# MCP4725_Breakout.net
KiCad netlist of a schematic drawn in EAGLE
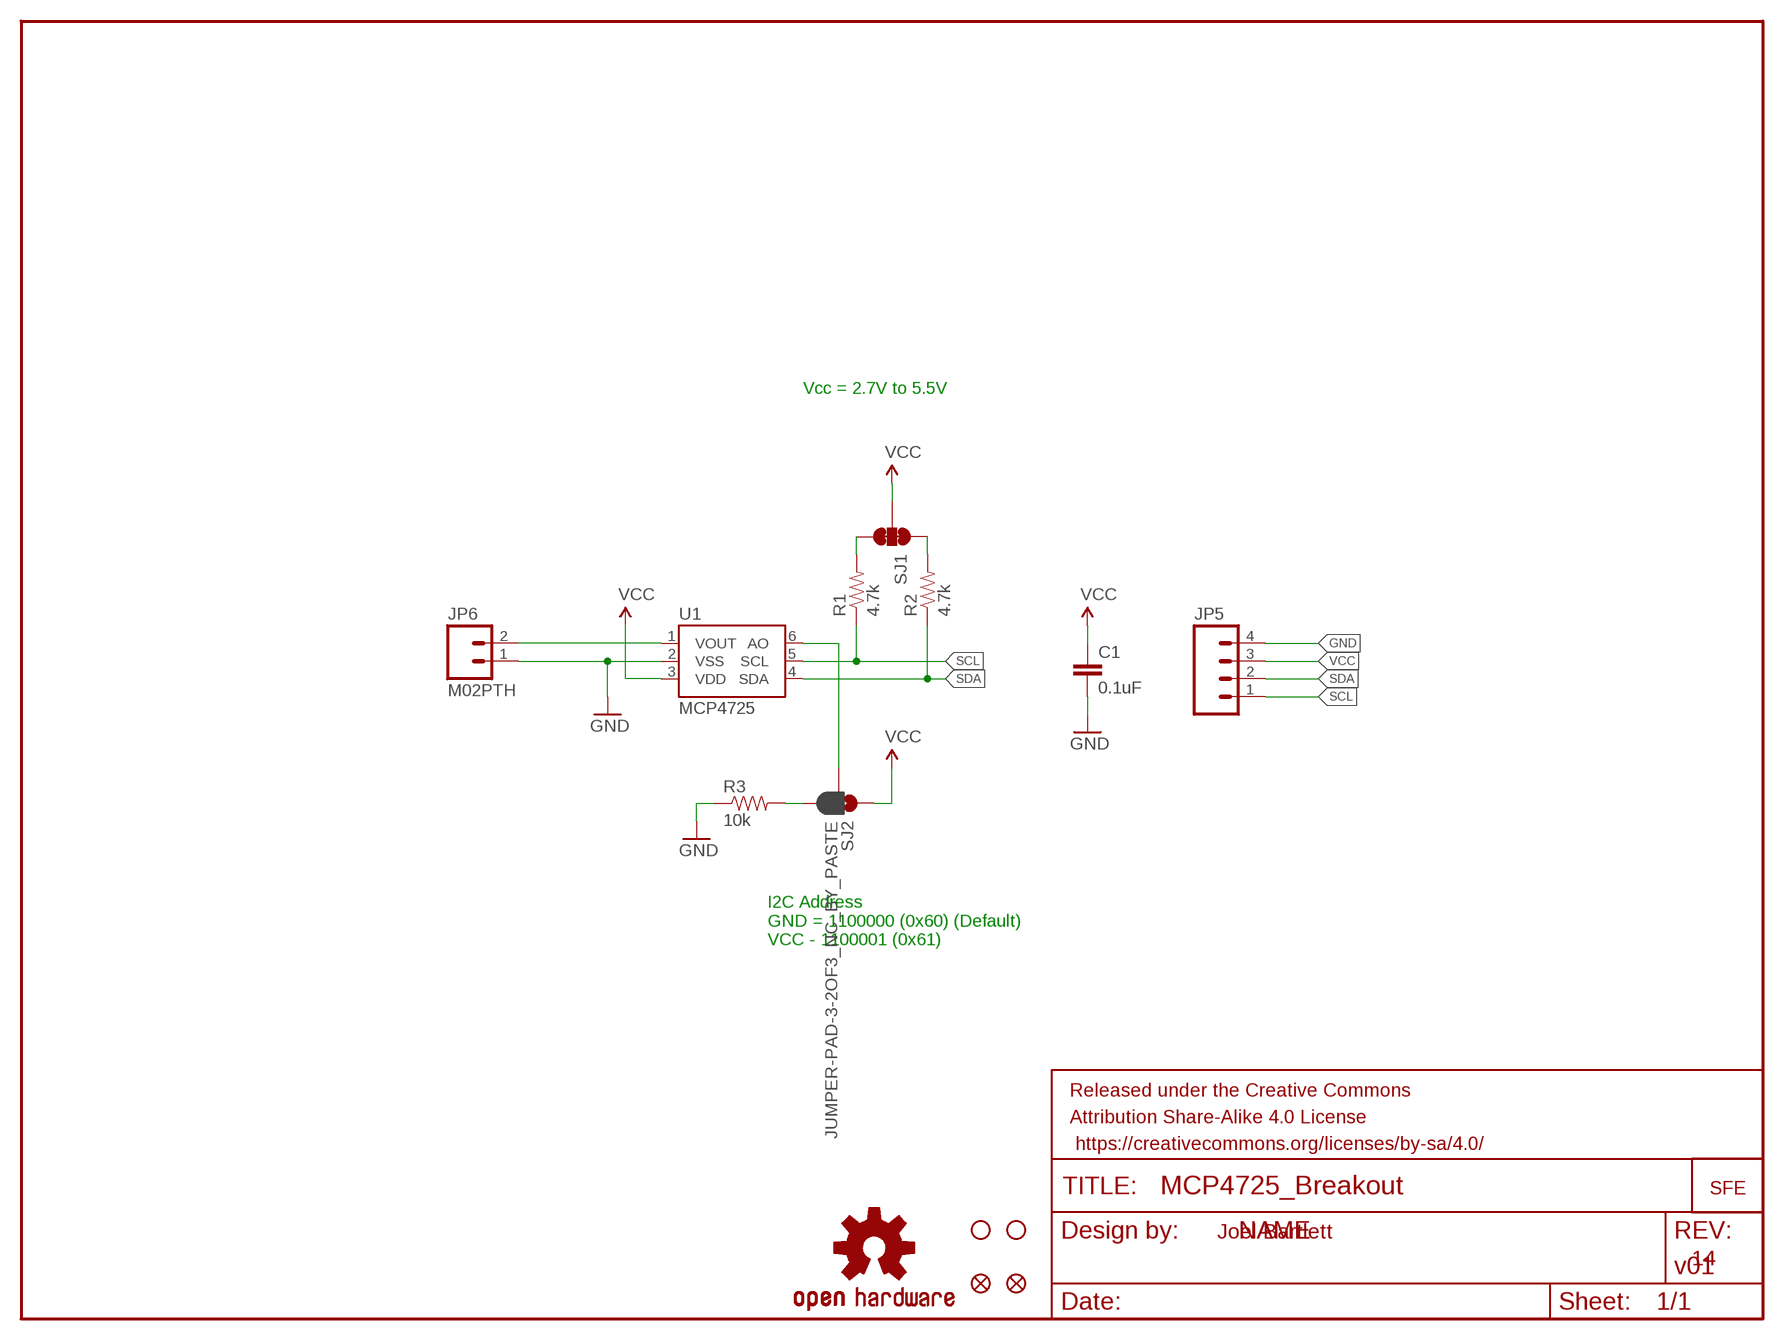
[diagram p0: schematic, sheet 1]

(export (version "E")
  (design (tool "Eeschema 10.0.6"))
  (components
    (comp (ref "C1")
      (value "0.1uF")
      (footprint "eagle-import:0603-CAP")
      (libsource (lib "eagle-import") (part "CAP0603-CAP"))
    )
    (comp (ref "FID1")
      (value "FIDUCIAL1X2")
      (footprint "eagle-import:FIDUCIAL-1X2")
      (libsource (lib "eagle-import") (part "FIDUCIAL1X2"))
    )
    (comp (ref "FID2")
      (value "FIDUCIAL1X2")
      (footprint "eagle-import:FIDUCIAL-1X2")
      (libsource (lib "eagle-import") (part "FIDUCIAL1X2"))
    )
    (comp (ref "FRAME2")
      (value "FRAME-LETTER")
      (footprint "eagle-import:CREATIVE_COMMONS")
      (fields (field (name "DESIGNER") "NAME"))
      (libsource (lib "eagle-import") (part "FRAME-LETTER"))
    )
    (comp (ref "GND")
      (value "LOGO-SFESK")
      (footprint "eagle-import:SFE-LOGO-FLAME")
      (libsource (lib "eagle-import") (part "LOGO-SFESK"))
    )
    (comp (ref "JP5")
      (value "M04PTH")
      (footprint "eagle-import:1X04")
      (libsource (lib "eagle-import") (part "M04PTH"))
    )
    (comp (ref "JP6")
      (value "M02PTH")
      (footprint "eagle-import:1X02")
      (libsource (lib "eagle-import") (part "M02PTH"))
    )
    (comp (ref "LOGO1")
      (value "OSHW-LOGOS")
      (footprint "eagle-import:OSHW-LOGO-S")
      (libsource (lib "eagle-import") (part "OSHW-LOGOS"))
    )
    (comp (ref "R1")
      (value "4.7k")
      (footprint "eagle-import:0603-RES")
      (libsource (lib "eagle-import") (part "RESISTOR0603-RES"))
    )
    (comp (ref "R2")
      (value "4.7k")
      (footprint "eagle-import:0603-RES")
      (libsource (lib "eagle-import") (part "RESISTOR0603-RES"))
    )
    (comp (ref "R3")
      (value "10k")
      (footprint "eagle-import:0603-RES")
      (libsource (lib "eagle-import") (part "RESISTOR0603-RES"))
    )
    (comp (ref "SJ1")
      (value "JUMPER-PAD-3-NC_BY_TRACE")
      (footprint "eagle-import:PAD-JUMPER-3-3OF3_NC_BY_TRACE_YES_SILK_FULL_BOX")
      (libsource (lib "eagle-import") (part "JUMPER-PAD-3-NC_BY_TRACE"))
    )
    (comp (ref "SJ2")
      (value "JUMPER-PAD-3-2OF3_NC_BY_PASTE")
      (footprint "eagle-import:PAD-JUMPER-3-2OF3_NC_BY_PASTE_YES_SILK_FULL_BOX")
      (libsource (lib "eagle-import") (part "JUMPER-PAD-3-2OF3_NC_BY_PASTE"))
    )
    (comp (ref "STANDOFF1")
      (value "STAND-OFF")
      (footprint "eagle-import:STAND-OFF")
      (libsource (lib "eagle-import") (part "STAND-OFF"))
    )
    (comp (ref "STANDOFF2")
      (value "STAND-OFF")
      (footprint "eagle-import:STAND-OFF")
      (libsource (lib "eagle-import") (part "STAND-OFF"))
    )
    (comp (ref "U1")
      (value "MCP4725")
      (footprint "eagle-import:SOT23-6")
      (libsource (lib "eagle-import") (part "MCP4725SOT-23"))
    )
  )
  (nets
    (net (code "1") (name "GND") (class "Default")
      (node (ref "C1") (pin "2") (pinfunction "2_2") (pintype "passive"))
      (node (ref "JP5") (pin "4") (pinfunction "4_4") (pintype "passive"))
      (node (ref "JP6") (pin "1") (pinfunction "1_1") (pintype "passive"))
      (node (ref "R3") (pin "1") (pinfunction "1_1") (pintype "passive"))
      (node (ref "U1") (pin "2") (pinfunction "VSS_2") (pintype "bidirectional"))
    )
    (net (code "2") (name "Net-(R1-Pad2)") (class "Default")
      (node (ref "R1") (pin "2") (pinfunction "2_2") (pintype "passive"))
      (node (ref "SJ1") (pin "3") (pinfunction "3_3") (pintype "passive"))
    )
    (net (code "3") (name "Net-(R2-Pad2)") (class "Default")
      (node (ref "R2") (pin "2") (pinfunction "2_2") (pintype "passive"))
      (node (ref "SJ1") (pin "1") (pinfunction "1_1") (pintype "passive"))
    )
    (net (code "4") (name "Net-(R3-Pad2)") (class "Default")
      (node (ref "R3") (pin "2") (pinfunction "2_2") (pintype "passive"))
      (node (ref "SJ2") (pin "3") (pinfunction "3_3") (pintype "passive"))
    )
    (net (code "5") (name "Net-(U1-AO)") (class "Default")
      (node (ref "SJ2") (pin "2") (pinfunction "2_2") (pintype "passive"))
      (node (ref "U1") (pin "6") (pinfunction "AO_6") (pintype "bidirectional"))
    )
    (net (code "6") (name "Net-(U1-VOUT)") (class "Default")
      (node (ref "JP6") (pin "2") (pinfunction "2_2") (pintype "passive"))
      (node (ref "U1") (pin "1") (pinfunction "VOUT_1") (pintype "bidirectional"))
    )
    (net (code "7") (name "SCL") (class "Default")
      (node (ref "JP5") (pin "1") (pinfunction "1_1") (pintype "passive"))
      (node (ref "R1") (pin "1") (pinfunction "1_1") (pintype "passive"))
      (node (ref "U1") (pin "5") (pinfunction "SCL_5") (pintype "bidirectional"))
    )
    (net (code "8") (name "SDA") (class "Default")
      (node (ref "JP5") (pin "2") (pinfunction "2_2") (pintype "passive"))
      (node (ref "R2") (pin "1") (pinfunction "1_1") (pintype "passive"))
      (node (ref "U1") (pin "4") (pinfunction "SDA_4") (pintype "bidirectional"))
    )
    (net (code "9") (name "VCC") (class "Default")
      (node (ref "C1") (pin "1") (pinfunction "1_1") (pintype "passive"))
      (node (ref "JP5") (pin "3") (pinfunction "3_3") (pintype "passive"))
      (node (ref "SJ1") (pin "2") (pinfunction "2_2") (pintype "passive"))
      (node (ref "SJ2") (pin "1") (pinfunction "1_1") (pintype "passive"))
      (node (ref "U1") (pin "3") (pinfunction "VDD_3") (pintype "bidirectional"))
    )
  )
)
